# MRCS-Remote-Switch-Motor-Controller.net
KiCad netlist of a schematic drawn in EAGLE
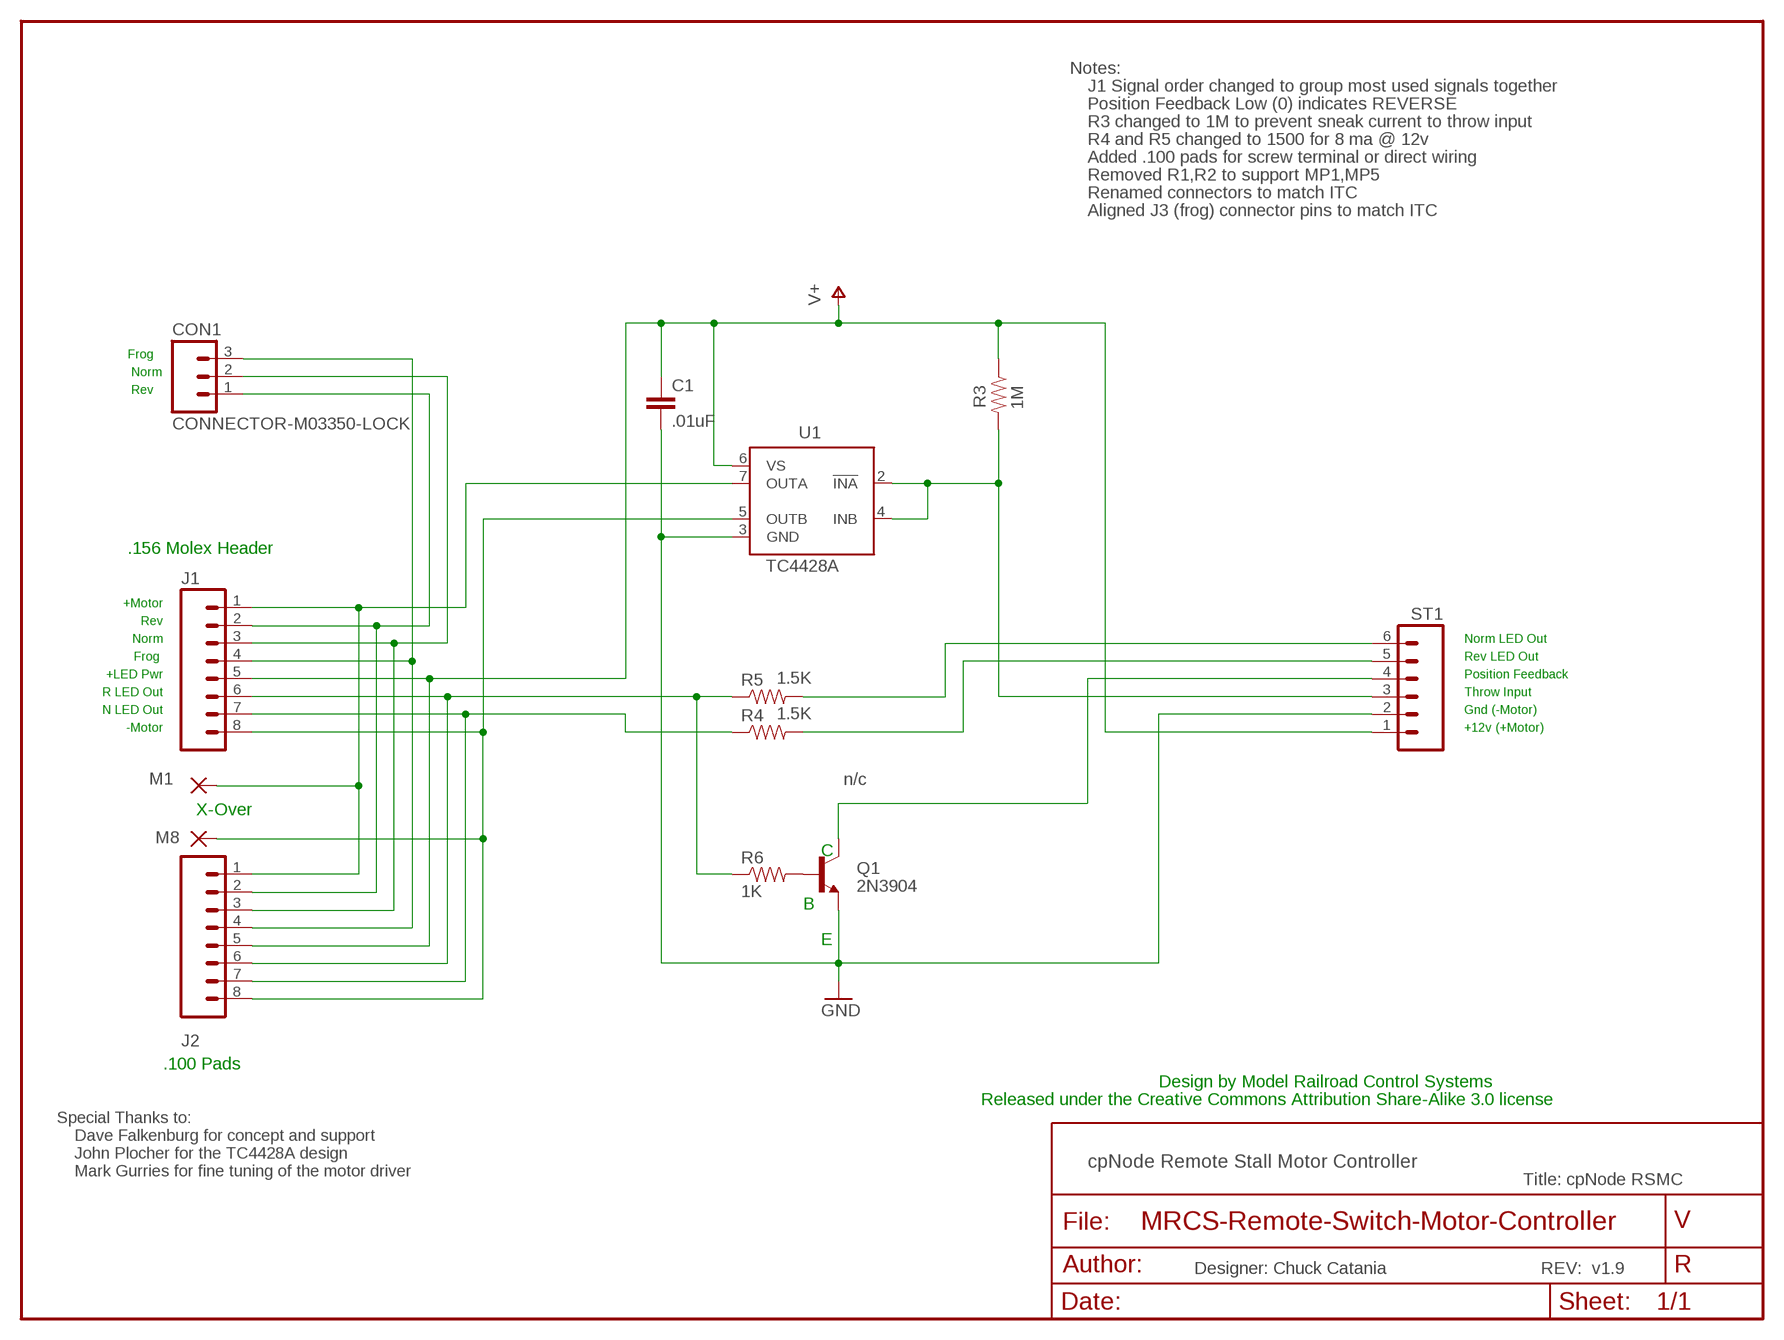
[diagram p0: schematic, sheet 1]

(export (version "E")
  (design (tool "Eeschema 10.0.6"))
  (components
    (comp (ref "C1")
      (value ".01uF")
      (footprint "eagle-import:CAP-PTH-SMALLEZ")
      (libsource (lib "eagle-import") (part "CAPEZ"))
    )
    (comp (ref "CON1")
      (value "CONNECTOR-M03350-LOCK")
      (footprint "eagle-import:1751251")
      (libsource (lib "eagle-import") (part "CONNECTOR-M03350-LOCK"))
    )
    (comp (ref "J1")
      (value "J1")
      (footprint "eagle-import:KK-156-8-F")
      (libsource (lib "eagle-import") (part "CONNECTOR-M081.56-F"))
    )
    (comp (ref "J2")
      (value "J2")
      (footprint "eagle-import:1X08_PIN1_NO_SILK")
      (libsource (lib "eagle-import") (part "M08"))
    )
    (comp (ref "M1")
      (value "WIREPAD2,54/1,1")
      (footprint "eagle-import:2,54_1,1")
      (libsource (lib "eagle-import") (part "WIREPAD2,54/1,1"))
    )
    (comp (ref "M8")
      (value "WIREPAD2,54/1,1")
      (footprint "eagle-import:2,54_1,1")
      (libsource (lib "eagle-import") (part "WIREPAD2,54/1,1"))
    )
    (comp (ref "Q1")
      (value "2N3904")
      (footprint "eagle-import:TO-92-MS013")
      (libsource (lib "eagle-import") (part "NPN-MS-013"))
    )
    (comp (ref "R3")
      (value "1M")
      (footprint "eagle-import:AXIAL-0.4-RES")
      (libsource (lib "eagle-import") (part "RPTH04"))
    )
    (comp (ref "R4")
      (value "1.5K")
      (footprint "eagle-import:AXIAL-0.4-RES")
      (libsource (lib "eagle-import") (part "RPTH04"))
    )
    (comp (ref "R5")
      (value "1.5K")
      (footprint "eagle-import:AXIAL-0.4-RES")
      (libsource (lib "eagle-import") (part "RPTH04"))
    )
    (comp (ref "R6")
      (value "1K")
      (footprint "eagle-import:AXIAL-0.4-RES")
      (libsource (lib "eagle-import") (part "RPTH04"))
    )
    (comp (ref "ST1")
      (value "M06LOCK")
      (footprint "eagle-import:1X06_LOCK")
      (libsource (lib "eagle-import") (part "M06LOCK"))
    )
    (comp (ref "U1")
      (value "TC4428A")
      (footprint "eagle-import:DIL08")
      (fields (field (name "MF") "INTERNATIONAL RECTIFIER(IR)") (field (name "MPN") "IR4428PBF"))
      (libsource (lib "eagle-import") (part "IR4428"))
    )
  )
  (nets
    (net (code "1") (name "GND") (class "Default")
      (node (ref "C1") (pin "2") (pinfunction "2_2") (pintype "passive"))
      (node (ref "Q1") (pin "1") (pinfunction "E_1") (pintype "passive"))
      (node (ref "ST1") (pin "2") (pinfunction "2_2") (pintype "passive"))
      (node (ref "U1") (pin "3") (pinfunction "GND_3") (pintype "power_in"))
    )
    (net (code "2") (name "Net-(CON1-Pad1)") (class "Default")
      (node (ref "CON1") (pin "1") (pinfunction "1_1") (pintype "passive"))
      (node (ref "J1") (pin "2") (pinfunction "2_2") (pintype "passive"))
      (node (ref "J2") (pin "2") (pinfunction "2_2") (pintype "passive"))
    )
    (net (code "3") (name "Net-(CON1-Pad2)") (class "Default")
      (node (ref "CON1") (pin "2") (pinfunction "2_2") (pintype "passive"))
      (node (ref "J1") (pin "3") (pinfunction "3_3") (pintype "passive"))
      (node (ref "J2") (pin "3") (pinfunction "3_3") (pintype "passive"))
    )
    (net (code "4") (name "Net-(CON1-Pad3)") (class "Default")
      (node (ref "CON1") (pin "3") (pinfunction "3_3") (pintype "passive"))
      (node (ref "J1") (pin "4") (pinfunction "4_4") (pintype "passive"))
      (node (ref "J2") (pin "4") (pinfunction "4_4") (pintype "passive"))
    )
    (net (code "5") (name "Net-(M1-P)") (class "Default")
      (node (ref "J1") (pin "1") (pinfunction "1_1") (pintype "passive"))
      (node (ref "J2") (pin "1") (pinfunction "1_1") (pintype "passive"))
      (node (ref "M1") (pin "1") (pinfunction "P_1") (pintype "passive"))
      (node (ref "U1") (pin "7") (pinfunction "OUTA_7") (pintype "output"))
    )
    (net (code "6") (name "Net-(M8-P)") (class "Default")
      (node (ref "J1") (pin "8") (pinfunction "8_8") (pintype "passive"))
      (node (ref "J2") (pin "8") (pinfunction "8_8") (pintype "passive"))
      (node (ref "M8") (pin "1") (pinfunction "P_1") (pintype "passive"))
      (node (ref "U1") (pin "5") (pinfunction "OUTB_5") (pintype "output"))
    )
    (net (code "7") (name "Net-(Q1-B)") (class "Default")
      (node (ref "Q1") (pin "2") (pinfunction "B_2") (pintype "passive"))
      (node (ref "R6") (pin "P$2") (pinfunction "2_P$2") (pintype "passive"))
    )
    (net (code "8") (name "Net-(Q1-C)") (class "Default")
      (node (ref "Q1") (pin "3") (pinfunction "C_3") (pintype "passive"))
      (node (ref "ST1") (pin "4") (pinfunction "4_4") (pintype "passive"))
    )
    (net (code "9") (name "Net-(R3-2)") (class "Default")
      (node (ref "R3") (pin "P$2") (pinfunction "2_P$2") (pintype "passive"))
      (node (ref "ST1") (pin "3") (pinfunction "3_3") (pintype "passive"))
      (node (ref "U1") (pin "2") (pinfunction "~{INA}_2") (pintype "input"))
      (node (ref "U1") (pin "4") (pinfunction "INB_4") (pintype "input"))
    )
    (net (code "10") (name "Net-(R4-1)") (class "Default")
      (node (ref "J1") (pin "7") (pinfunction "7_7") (pintype "passive"))
      (node (ref "J2") (pin "7") (pinfunction "7_7") (pintype "passive"))
      (node (ref "R4") (pin "P$1") (pinfunction "1_P$1") (pintype "passive"))
    )
    (net (code "11") (name "Net-(R4-2)") (class "Default")
      (node (ref "R4") (pin "P$2") (pinfunction "2_P$2") (pintype "passive"))
      (node (ref "ST1") (pin "5") (pinfunction "5_5") (pintype "passive"))
    )
    (net (code "12") (name "Net-(R5-1)") (class "Default")
      (node (ref "J1") (pin "6") (pinfunction "6_6") (pintype "passive"))
      (node (ref "J2") (pin "6") (pinfunction "6_6") (pintype "passive"))
      (node (ref "R5") (pin "P$1") (pinfunction "1_P$1") (pintype "passive"))
      (node (ref "R6") (pin "P$1") (pinfunction "1_P$1") (pintype "passive"))
    )
    (net (code "13") (name "Net-(R5-2)") (class "Default")
      (node (ref "R5") (pin "P$2") (pinfunction "2_P$2") (pintype "passive"))
      (node (ref "ST1") (pin "6") (pinfunction "6_6") (pintype "passive"))
    )
    (net (code "14") (name "V+") (class "Default")
      (node (ref "C1") (pin "1") (pinfunction "1_1") (pintype "passive"))
      (node (ref "J1") (pin "5") (pinfunction "5_5") (pintype "passive"))
      (node (ref "J2") (pin "5") (pinfunction "5_5") (pintype "passive"))
      (node (ref "R3") (pin "P$1") (pinfunction "1_P$1") (pintype "passive"))
      (node (ref "ST1") (pin "1") (pinfunction "1_1") (pintype "passive"))
      (node (ref "U1") (pin "6") (pinfunction "VS_6") (pintype "power_in"))
    )
  )
)
